# PCI_Express.net
KiCad netlist of a schematic drawn in Altium Designer
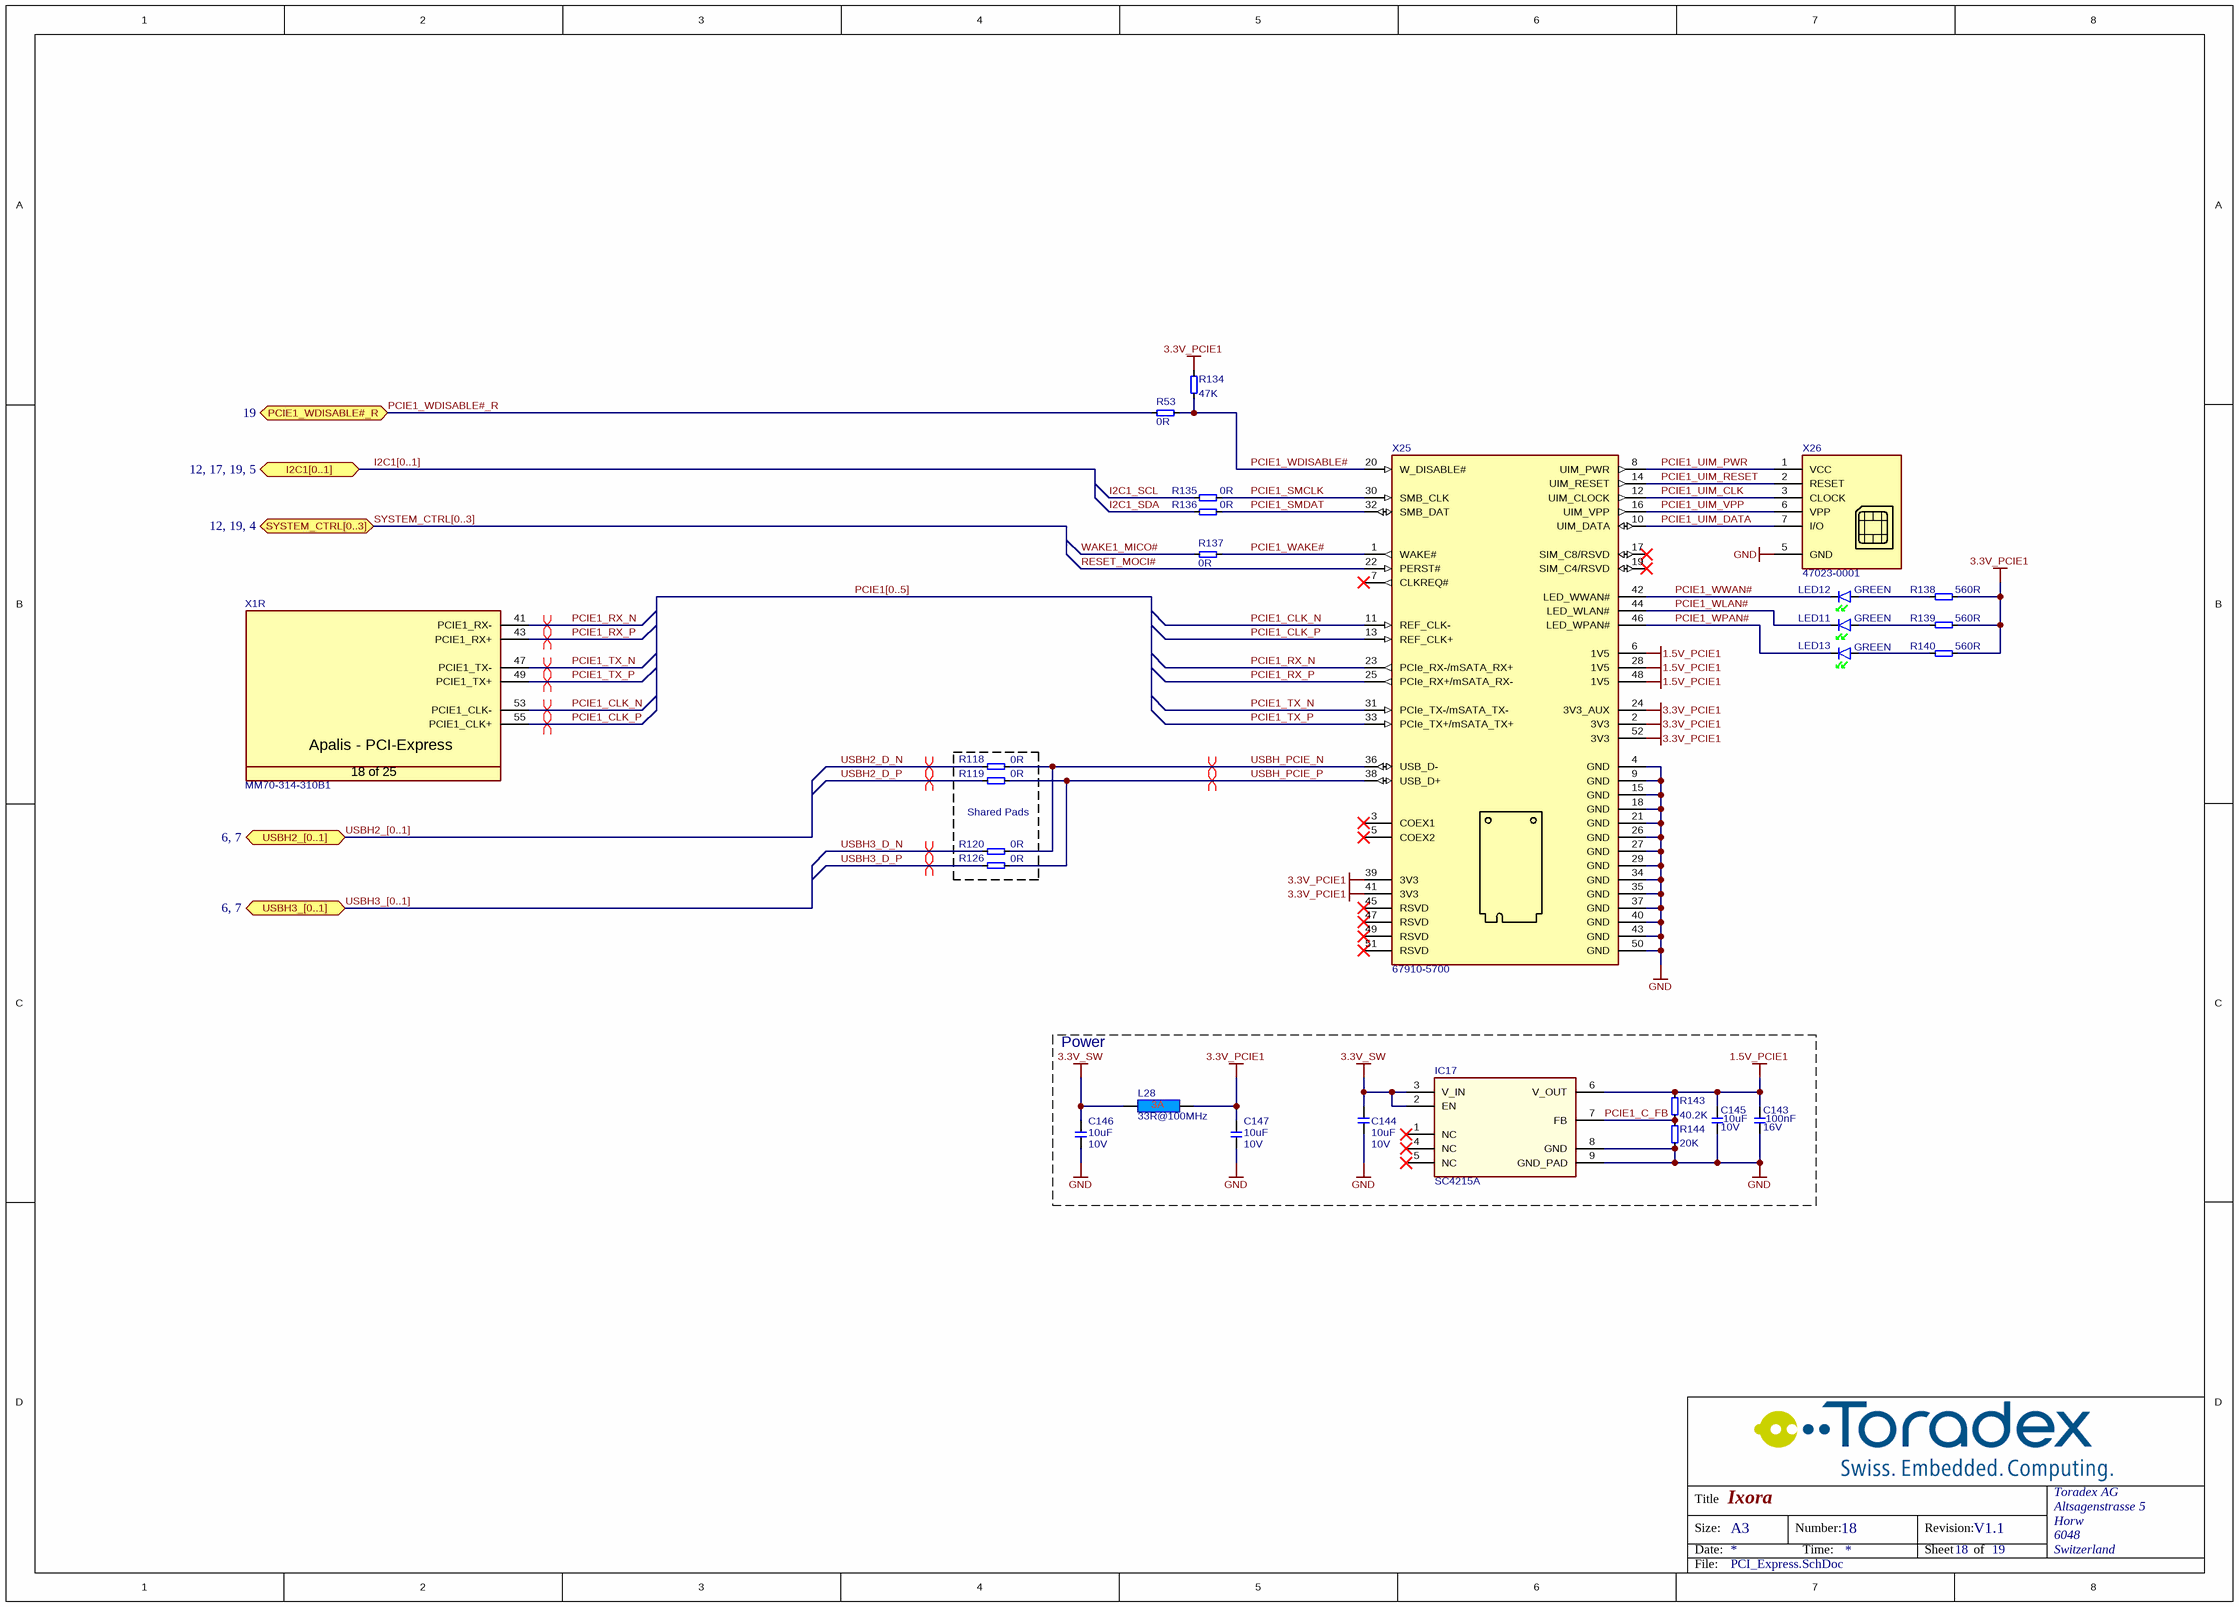
[diagram p0: PCI_Express.SchDoc]

(export (version "E")
  (design (tool "Eeschema 10.0.6"))
  (components
    (comp (ref "C143")
      (value "100nF")
      (footprint "CAPC1005X60N")
      (description "Capacitor Ceramic X7R 100nF 16V 10% 0402")
      (fields (field (name "TOLERANCE") "10%") (field (name "RATING") "16V"))
      (libsource (lib "Ixora") (part "C-X7R-100nF-16V-10%-0402"))
    )
    (comp (ref "C144")
      (value "10uF")
      (footprint "T_CAPC0603X33N")
      (description "Capacitor Ceramic X5R 10uF 10V 20% 0603")
      (fields (field (name "TOLERANCE") "20%") (field (name "RATING") "10V"))
      (libsource (lib "Ixora") (part "C-X5R-10uF-10V-20%-0603"))
    )
    (comp (ref "C145")
      (value "10uF")
      (footprint "T_CAPC0603X33N")
      (description "Capacitor Ceramic X5R 10uF 10V 20% 0603")
      (fields (field (name "TOLERANCE") "20%") (field (name "RATING") "10V"))
      (libsource (lib "Ixora") (part "C-X5R-10uF-10V-20%-0603"))
    )
    (comp (ref "C146")
      (value "10uF")
      (footprint "T_CAPC0603X33N")
      (description "Capacitor Ceramic X5R 10uF 10V 20% 0603")
      (fields (field (name "TOLERANCE") "20%") (field (name "RATING") "10V"))
      (libsource (lib "Ixora") (part "C-X5R-10uF-10V-20%-0603"))
    )
    (comp (ref "C147")
      (value "10uF")
      (footprint "T_CAPC0603X33N")
      (description "Capacitor Ceramic X5R 10uF 10V 20% 0603")
      (fields (field (name "TOLERANCE") "20%") (field (name "RATING") "10V"))
      (libsource (lib "Ixora") (part "C-X5R-10uF-10V-20%-0603"))
    )
    (comp (ref "IC17")
      (value "IC-Semtech-SC4215A")
      (footprint "SOIC127P650X175_HS-8N")
      (description "LDO TO 2A")
      (fields (field (name "MANUFACTURER PART NO.") "SC4215A"))
      (libsource (lib "Ixora") (part "IC-Semtech-SC4215A"))
    )
    (comp (ref "L28")
      (value "33R@100MHz")
      (footprint "INDC1608X95N")
      (description "33R@100MHz 3A EMI FILTER")
      (fields (field (name "TOLERANCE") "25%"))
      (libsource (lib "Ixora") (part "L-33R@100MHz-3A-25%-0603"))
    )
    (comp (ref "LED11")
      (value "APA1606CGCK")
      (footprint "T_Kingbright_APA1606CGCK")
      (description "LED green Kingbright APA1606CGCK")
      (fields (field (name "COLOR") "GREEN"))
      (libsource (lib "Ixora") (part "LED-Kingbright-APA1606CGCK"))
    )
    (comp (ref "LED12")
      (value "APA1606CGCK")
      (footprint "T_Kingbright_APA1606CGCK")
      (description "LED green Kingbright APA1606CGCK")
      (fields (field (name "COLOR") "GREEN"))
      (libsource (lib "Ixora") (part "LED-Kingbright-APA1606CGCK"))
    )
    (comp (ref "LED13")
      (value "APA1606CGCK")
      (footprint "T_Kingbright_APA1606CGCK")
      (description "LED green Kingbright APA1606CGCK")
      (fields (field (name "COLOR") "GREEN"))
      (libsource (lib "Ixora") (part "LED-Kingbright-APA1606CGCK"))
    )
    (comp (ref "R53")
      (value "0R")
      (footprint "T_RESC0603X30N")
      (description "Resistor 0 ohm 63mW 1% 0603")
      (fields (field (name "TOLERANCE") "1%"))
      (libsource (lib "Ixora") (part "R-0R-63mW-1%-0603"))
    )
    (comp (ref "R118")
      (value "0R")
      (footprint "T_RESC0603X30N")
      (description "Resistor 0 ohm 63mW 1% 0603")
      (fields (field (name "TOLERANCE") "1%"))
      (libsource (lib "Ixora") (part "R-0R-63mW-1%-0603"))
    )
    (comp (ref "R119")
      (value "0R")
      (footprint "T_RESC0603X30N")
      (description "Resistor 0 ohm 63mW 1% 0603")
      (fields (field (name "TOLERANCE") "1%"))
      (libsource (lib "Ixora") (part "R-0R-63mW-1%-0603"))
    )
    (comp (ref "R120")
      (value "0R")
      (footprint "T_RESC0603X30N")
      (description "Resistor 0 ohm 63mW 1% 0603")
      (fields (field (name "TOLERANCE") "1%"))
      (libsource (lib "Ixora") (part "R-0R-63mW-1%-0603"))
    )
    (comp (ref "R126")
      (value "0R")
      (footprint "T_RESC0603X30N")
      (description "Resistor 0 ohm 63mW 1% 0603")
      (fields (field (name "TOLERANCE") "1%"))
      (libsource (lib "Ixora") (part "R-0R-63mW-1%-0603"))
    )
    (comp (ref "R134")
      (value "47K")
      (footprint "T_RESC0603X30N")
      (description "Resistor 47 Kohm 63mW 5% 0603")
      (fields (field (name "TOLERANCE") "5%"))
      (libsource (lib "Ixora") (part "R-47KR-63mW-5%-0603"))
    )
    (comp (ref "R135")
      (value "0R")
      (footprint "RESC1005X40N")
      (description "Resistor 0 ohm 63mW 1% 0402")
      (fields (field (name "TOLERANCE") "1%"))
      (libsource (lib "Ixora") (part "R-0R-63mW-1%-0402"))
    )
    (comp (ref "R136")
      (value "0R")
      (footprint "RESC1005X40N")
      (description "Resistor 0 ohm 63mW 1% 0402")
      (fields (field (name "TOLERANCE") "1%"))
      (libsource (lib "Ixora") (part "R-0R-63mW-1%-0402"))
    )
    (comp (ref "R137")
      (value "0R")
      (footprint "T_RESC0603X30N")
      (description "Resistor 0 ohm 63mW 1% 0603")
      (fields (field (name "TOLERANCE") "1%"))
      (libsource (lib "Ixora") (part "R-0R-63mW-1%-0603"))
    )
    (comp (ref "R138")
      (value "560R")
      (footprint "RESC1005X40N")
      (description "Resistor 560 ohm 63mW 5% 0402")
      (fields (field (name "TOLERANCE") "5%"))
      (libsource (lib "Ixora") (part "R-560R-63mW-5%-0402"))
    )
    (comp (ref "R139")
      (value "560R")
      (footprint "RESC1005X40N")
      (description "Resistor 560 ohm 63mW 5% 0402")
      (fields (field (name "TOLERANCE") "5%"))
      (libsource (lib "Ixora") (part "R-560R-63mW-5%-0402"))
    )
    (comp (ref "R140")
      (value "560R")
      (footprint "RESC1005X40N")
      (description "Resistor 560 ohm 63mW 5% 0402")
      (fields (field (name "TOLERANCE") "5%"))
      (libsource (lib "Ixora") (part "R-560R-63mW-5%-0402"))
    )
    (comp (ref "R143")
      (value "40.2K")
      (footprint "RESC1005X40N")
      (description "Resistor 40.2 Kohm 63mW 1% 0402")
      (fields (field (name "TOLERANCE") "1%"))
      (libsource (lib "Ixora") (part "R-40.2KR-63mW-1%-0402"))
    )
    (comp (ref "R144")
      (value "20K")
      (footprint "RESC1005X40N")
      (description "Resistor 20 Kohm 63mW 1% 0402")
      (fields (field (name "TOLERANCE") "1%"))
      (libsource (lib "Ixora") (part "R-20KR-63mW-1%-0402"))
    )
    (comp (ref "X1")
      (value "CON-JAE-MM70-314-310B1-314-0.5mm")
      (footprint "T_JAE_MM70-314-310B1")
      (description "MXM3 Connector")
      (fields (field (name "MANUFACTURER PART NO.") "MM70-314-310B1"))
      (libsource (lib "Ixora") (part "CON-JAE-MM70-314-310B1-314-0.5mm"))
    )
    (comp (ref "X25")
      (value "67910-5700")
      (footprint "T_Molex_67910-5700")
      (description "PCIe_Mini Card Holder")
      (fields (field (name "PART NO.") "67910-5700"))
      (libsource (lib "Ixora") (part "CON-Molex-67910-5700"))
    )
    (comp (ref "X26")
      (value "47023-0001")
      (footprint "T_Molex_47023-0001")
      (description "6 Contacts Mini Sim Card Holder")
      (fields (field (name "PART NO.") "47023-0001"))
      (libsource (lib "Ixora") (part "CON-Molex-47023-0001"))
    )
  )
  (nets
    (net (code "18") (name "/I2C1_SCL") (class "Default")
      (node (ref "R135") (pin "1") (pinfunction "1_1") (pintype "passive"))
    )
    (net (code "19") (name "/I2C1_SDA") (class "Default")
      (node (ref "R136") (pin "1") (pinfunction "1_1") (pintype "passive"))
    )
    (net (code "21") (name "/PCIE1_CLK_N") (class "Default")
      (node (ref "X1") (pin "53") (pinfunction "PCIE1_CLK-_53") (pintype "passive"))
      (node (ref "X25") (pin "11") (pinfunction "REF_CLK-_11") (pintype "input"))
    )
    (net (code "22") (name "/PCIE1_CLK_P") (class "Default")
      (node (ref "X1") (pin "55") (pinfunction "PCIE1_CLK+_55") (pintype "passive"))
      (node (ref "X25") (pin "13") (pinfunction "REF_CLK+_13") (pintype "input"))
    )
    (net (code "23") (name "/PCIE1_C_FB") (class "Default")
      (node (ref "IC17") (pin "7") (pinfunction "FB_7") (pintype "passive"))
      (node (ref "R143") (pin "1") (pinfunction "1_1") (pintype "passive"))
      (node (ref "R144") (pin "2") (pinfunction "2_2") (pintype "passive"))
    )
    (net (code "24") (name "/PCIE1_RX_N") (class "Default")
      (node (ref "X1") (pin "41") (pinfunction "PCIE1_RX-_41") (pintype "passive"))
      (node (ref "X25") (pin "23") (pinfunction "PCIe_RX-/mSATA_RX+_23") (pintype "output"))
    )
    (net (code "25") (name "/PCIE1_RX_P") (class "Default")
      (node (ref "X1") (pin "43") (pinfunction "PCIE1_RX+_43") (pintype "passive"))
      (node (ref "X25") (pin "25") (pinfunction "PCIe_RX+/mSATA_RX-_25") (pintype "output"))
    )
    (net (code "26") (name "/PCIE1_SMCLK") (class "Default")
      (node (ref "R135") (pin "2") (pinfunction "2_2") (pintype "passive"))
      (node (ref "X25") (pin "30") (pinfunction "SMB_CLK_30") (pintype "input"))
    )
    (net (code "27") (name "/PCIE1_SMDAT") (class "Default")
      (node (ref "R136") (pin "2") (pinfunction "2_2") (pintype "passive"))
      (node (ref "X25") (pin "32") (pinfunction "SMB_DAT_32") (pintype "bidirectional"))
    )
    (net (code "28") (name "/PCIE1_TX_N") (class "Default")
      (node (ref "X1") (pin "47") (pinfunction "PCIE1_TX-_47") (pintype "passive"))
      (node (ref "X25") (pin "31") (pinfunction "PCIe_TX-/mSATA_TX-_31") (pintype "input"))
    )
    (net (code "29") (name "/PCIE1_TX_P") (class "Default")
      (node (ref "X1") (pin "49") (pinfunction "PCIE1_TX+_49") (pintype "passive"))
      (node (ref "X25") (pin "33") (pinfunction "PCIe_TX+/mSATA_TX+_33") (pintype "input"))
    )
    (net (code "30") (name "/PCIE1_UIM_CLK") (class "Default")
      (node (ref "X25") (pin "12") (pinfunction "UIM_CLOCK_12") (pintype "output"))
      (node (ref "X26") (pin "3") (pinfunction "CLOCK_3") (pintype "passive"))
    )
    (net (code "31") (name "/PCIE1_UIM_DATA") (class "Default")
      (node (ref "X25") (pin "10") (pinfunction "UIM_DATA_10") (pintype "bidirectional"))
      (node (ref "X26") (pin "7") (pinfunction "I/O_7") (pintype "passive"))
    )
    (net (code "32") (name "/PCIE1_UIM_PWR") (class "Default")
      (node (ref "X25") (pin "8") (pinfunction "UIM_PWR_8") (pintype "output"))
      (node (ref "X26") (pin "1") (pinfunction "VCC_1") (pintype "passive"))
    )
    (net (code "33") (name "/PCIE1_UIM_RESET") (class "Default")
      (node (ref "X25") (pin "14") (pinfunction "UIM_RESET_14") (pintype "output"))
      (node (ref "X26") (pin "2") (pinfunction "RESET_2") (pintype "passive"))
    )
    (net (code "34") (name "/PCIE1_UIM_VPP") (class "Default")
      (node (ref "X25") (pin "16") (pinfunction "UIM_VPP_16") (pintype "output"))
      (node (ref "X26") (pin "6") (pinfunction "VPP_6") (pintype "passive"))
    )
    (net (code "35") (name "/PCIE1_WAKE#") (class "Default")
      (node (ref "R137") (pin "2") (pinfunction "2_2") (pintype "passive"))
      (node (ref "X25") (pin "1") (pinfunction "WAKE#_1") (pintype "output"))
    )
    (net (code "36") (name "/PCIE1_WDISABLE#") (class "Default")
      (node (ref "R134") (pin "1") (pinfunction "1_1") (pintype "passive"))
      (node (ref "R53") (pin "1") (pinfunction "1_1") (pintype "passive"))
      (node (ref "X25") (pin "20") (pinfunction "W_DISABLE#_20") (pintype "input"))
    )
    (net (code "37") (name "/PCIE1_WDISABLE#_R") (class "Default")
      (node (ref "R53") (pin "2") (pinfunction "2_2") (pintype "passive"))
    )
    (net (code "38") (name "/PCIE1_WLAN#") (class "Default")
      (node (ref "LED11") (pin "1") (pinfunction "K_1") (pintype "passive"))
      (node (ref "X25") (pin "44") (pinfunction "LED_WLAN#_44") (pintype "open_collector"))
    )
    (net (code "39") (name "/PCIE1_WPAN#") (class "Default")
      (node (ref "LED13") (pin "1") (pinfunction "K_1") (pintype "passive"))
      (node (ref "X25") (pin "46") (pinfunction "LED_WPAN#_46") (pintype "open_collector"))
    )
    (net (code "40") (name "/PCIE1_WWAN#") (class "Default")
      (node (ref "LED12") (pin "1") (pinfunction "K_1") (pintype "passive"))
      (node (ref "X25") (pin "42") (pinfunction "LED_WWAN#_42") (pintype "open_collector"))
    )
    (net (code "41") (name "/RESET_MOCI#") (class "Default")
      (node (ref "X25") (pin "22") (pinfunction "PERST#_22") (pintype "input"))
    )
    (net (code "43") (name "/USBH2_D_N") (class "Default")
      (node (ref "R118") (pin "1") (pinfunction "1_1") (pintype "passive"))
    )
    (net (code "44") (name "/USBH2_D_P") (class "Default")
      (node (ref "R119") (pin "1") (pinfunction "1_1") (pintype "passive"))
    )
    (net (code "46") (name "/USBH3_D_N") (class "Default")
      (node (ref "R120") (pin "1") (pinfunction "1_1") (pintype "passive"))
    )
    (net (code "47") (name "/USBH3_D_P") (class "Default")
      (node (ref "R126") (pin "1") (pinfunction "1_1") (pintype "passive"))
    )
    (net (code "49") (name "/USBH_PCIE_N") (class "Default")
      (node (ref "R118") (pin "2") (pinfunction "2_2") (pintype "passive"))
      (node (ref "R120") (pin "2") (pinfunction "2_2") (pintype "passive"))
      (node (ref "X25") (pin "36") (pinfunction "USB_D-_36") (pintype "bidirectional"))
    )
    (net (code "50") (name "/USBH_PCIE_P") (class "Default")
      (node (ref "R119") (pin "2") (pinfunction "2_2") (pintype "passive"))
      (node (ref "R126") (pin "2") (pinfunction "2_2") (pintype "passive"))
      (node (ref "X25") (pin "38") (pinfunction "USB_D+_38") (pintype "bidirectional"))
    )
    (net (code "51") (name "/WAKE1_MICO#") (class "Default")
      (node (ref "R137") (pin "1") (pinfunction "1_1") (pintype "passive"))
    )
    (net (code "52") (name "1.5V_PCIE1") (class "Default")
      (node (ref "C143") (pin "2") (pinfunction "2_2") (pintype "passive"))
      (node (ref "C145") (pin "2") (pinfunction "2_2") (pintype "passive"))
      (node (ref "IC17") (pin "6") (pinfunction "V_OUT_6") (pintype "passive"))
      (node (ref "R143") (pin "2") (pinfunction "2_2") (pintype "passive"))
      (node (ref "X25") (pin "28") (pinfunction "1V5_28") (pintype "power_in"))
      (node (ref "X25") (pin "48") (pinfunction "1V5_48") (pintype "power_in"))
      (node (ref "X25") (pin "6") (pinfunction "1V5_6") (pintype "power_in"))
    )
    (net (code "53") (name "3.3V_PCIE1") (class "Default")
      (node (ref "C147") (pin "2") (pinfunction "2_2") (pintype "passive"))
      (node (ref "L28") (pin "2") (pinfunction "2_2") (pintype "passive"))
      (node (ref "R134") (pin "2") (pinfunction "2_2") (pintype "passive"))
      (node (ref "R138") (pin "1") (pinfunction "1_1") (pintype "passive"))
      (node (ref "R139") (pin "1") (pinfunction "1_1") (pintype "passive"))
      (node (ref "R140") (pin "1") (pinfunction "1_1") (pintype "passive"))
      (node (ref "X25") (pin "2") (pinfunction "3V3_2") (pintype "power_in"))
      (node (ref "X25") (pin "24") (pinfunction "3V3_AUX_24") (pintype "power_in"))
      (node (ref "X25") (pin "39") (pinfunction "3V3_39") (pintype "passive"))
      (node (ref "X25") (pin "41") (pinfunction "3V3_41") (pintype "passive"))
      (node (ref "X25") (pin "52") (pinfunction "3V3_52") (pintype "power_in"))
    )
    (net (code "54") (name "3.3V_SW") (class "Default")
      (node (ref "C144") (pin "2") (pinfunction "2_2") (pintype "passive"))
      (node (ref "C146") (pin "2") (pinfunction "2_2") (pintype "passive"))
      (node (ref "IC17") (pin "2") (pinfunction "EN_2") (pintype "passive"))
      (node (ref "IC17") (pin "3") (pinfunction "V_IN_3") (pintype "passive"))
      (node (ref "L28") (pin "1") (pinfunction "1_1") (pintype "passive"))
    )
    (net (code "55") (name "GND") (class "Default")
      (node (ref "C143") (pin "1") (pinfunction "1_1") (pintype "passive"))
      (node (ref "C144") (pin "1") (pinfunction "1_1") (pintype "passive"))
      (node (ref "C145") (pin "1") (pinfunction "1_1") (pintype "passive"))
      (node (ref "C146") (pin "1") (pinfunction "1_1") (pintype "passive"))
      (node (ref "C147") (pin "1") (pinfunction "1_1") (pintype "passive"))
      (node (ref "IC17") (pin "8") (pinfunction "GND_8") (pintype "passive"))
      (node (ref "IC17") (pin "9") (pinfunction "GND_PAD_9") (pintype "passive"))
      (node (ref "R144") (pin "1") (pinfunction "1_1") (pintype "passive"))
      (node (ref "X25") (pin "15") (pinfunction "GND_15") (pintype "power_in"))
      (node (ref "X25") (pin "18") (pinfunction "GND_18") (pintype "power_in"))
      (node (ref "X25") (pin "21") (pinfunction "GND_21") (pintype "power_in"))
      (node (ref "X25") (pin "26") (pinfunction "GND_26") (pintype "power_in"))
      (node (ref "X25") (pin "27") (pinfunction "GND_27") (pintype "power_in"))
      (node (ref "X25") (pin "29") (pinfunction "GND_29") (pintype "power_in"))
      (node (ref "X25") (pin "34") (pinfunction "GND_34") (pintype "power_in"))
      (node (ref "X25") (pin "35") (pinfunction "GND_35") (pintype "power_in"))
      (node (ref "X25") (pin "37") (pinfunction "GND_37") (pintype "power_in"))
      (node (ref "X25") (pin "4") (pinfunction "GND_4") (pintype "power_in"))
      (node (ref "X25") (pin "40") (pinfunction "GND_40") (pintype "power_in"))
      (node (ref "X25") (pin "43") (pinfunction "GND_43") (pintype "power_in"))
      (node (ref "X25") (pin "50") (pinfunction "GND_50") (pintype "power_in"))
      (node (ref "X25") (pin "9") (pinfunction "GND_9") (pintype "power_in"))
      (node (ref "X26") (pin "5") (pinfunction "GND_5") (pintype "passive"))
    )
    (net (code "56") (name "Net-(LED11-A)") (class "Default")
      (node (ref "LED11") (pin "2") (pinfunction "A_2") (pintype "passive"))
      (node (ref "R139") (pin "2") (pinfunction "2_2") (pintype "passive"))
    )
    (net (code "57") (name "Net-(LED12-A)") (class "Default")
      (node (ref "LED12") (pin "2") (pinfunction "A_2") (pintype "passive"))
      (node (ref "R138") (pin "2") (pinfunction "2_2") (pintype "passive"))
    )
    (net (code "58") (name "Net-(LED13-A)") (class "Default")
      (node (ref "LED13") (pin "2") (pinfunction "A_2") (pintype "passive"))
      (node (ref "R140") (pin "2") (pinfunction "2_2") (pintype "passive"))
    )
    (net (code "59") (name "unconnected-(IC17-NC-Pad1)") (class "Default")
      (node (ref "IC17") (pin "1") (pinfunction "NC_1") (pintype "passive+no_connect"))
    )
    (net (code "60") (name "unconnected-(IC17-NC-Pad4)") (class "Default")
      (node (ref "IC17") (pin "4") (pinfunction "NC_4") (pintype "passive+no_connect"))
    )
    (net (code "61") (name "unconnected-(IC17-NC-Pad5)") (class "Default")
      (node (ref "IC17") (pin "5") (pinfunction "NC_5") (pintype "passive+no_connect"))
    )
    (net (code "62") (name "unconnected-(X25-CLKREQ#-Pad7)") (class "Default")
      (node (ref "X25") (pin "7") (pinfunction "CLKREQ#_7") (pintype "output+no_connect"))
    )
    (net (code "63") (name "unconnected-(X25-COEX1-Pad3)") (class "Default")
      (node (ref "X25") (pin "3") (pinfunction "COEX1_3") (pintype "passive+no_connect"))
    )
    (net (code "64") (name "unconnected-(X25-COEX2-Pad5)") (class "Default")
      (node (ref "X25") (pin "5") (pinfunction "COEX2_5") (pintype "passive+no_connect"))
    )
    (net (code "65") (name "unconnected-(X25-RSVD-Pad45)") (class "Default")
      (node (ref "X25") (pin "45") (pinfunction "RSVD_45") (pintype "passive+no_connect"))
    )
    (net (code "66") (name "unconnected-(X25-RSVD-Pad47)") (class "Default")
      (node (ref "X25") (pin "47") (pinfunction "RSVD_47") (pintype "passive+no_connect"))
    )
    (net (code "67") (name "unconnected-(X25-RSVD-Pad49)") (class "Default")
      (node (ref "X25") (pin "49") (pinfunction "RSVD_49") (pintype "passive+no_connect"))
    )
    (net (code "68") (name "unconnected-(X25-RSVD-Pad51)") (class "Default")
      (node (ref "X25") (pin "51") (pinfunction "RSVD_51") (pintype "passive+no_connect"))
    )
    (net (code "69") (name "unconnected-(X25-SIM_C4{slash}RSVD-Pad19)") (class "Default")
      (node (ref "X25") (pin "19") (pinfunction "SIM_C4/RSVD_19") (pintype "bidirectional+no_connect"))
    )
    (net (code "70") (name "unconnected-(X25-SIM_C8{slash}RSVD-Pad17)") (class "Default")
      (node (ref "X25") (pin "17") (pinfunction "SIM_C8/RSVD_17") (pintype "bidirectional+no_connect"))
    )
  )
)
